# P-MT3620RDB-1-0_FTDI.net
KiCad netlist of a schematic drawn in Altium Designer
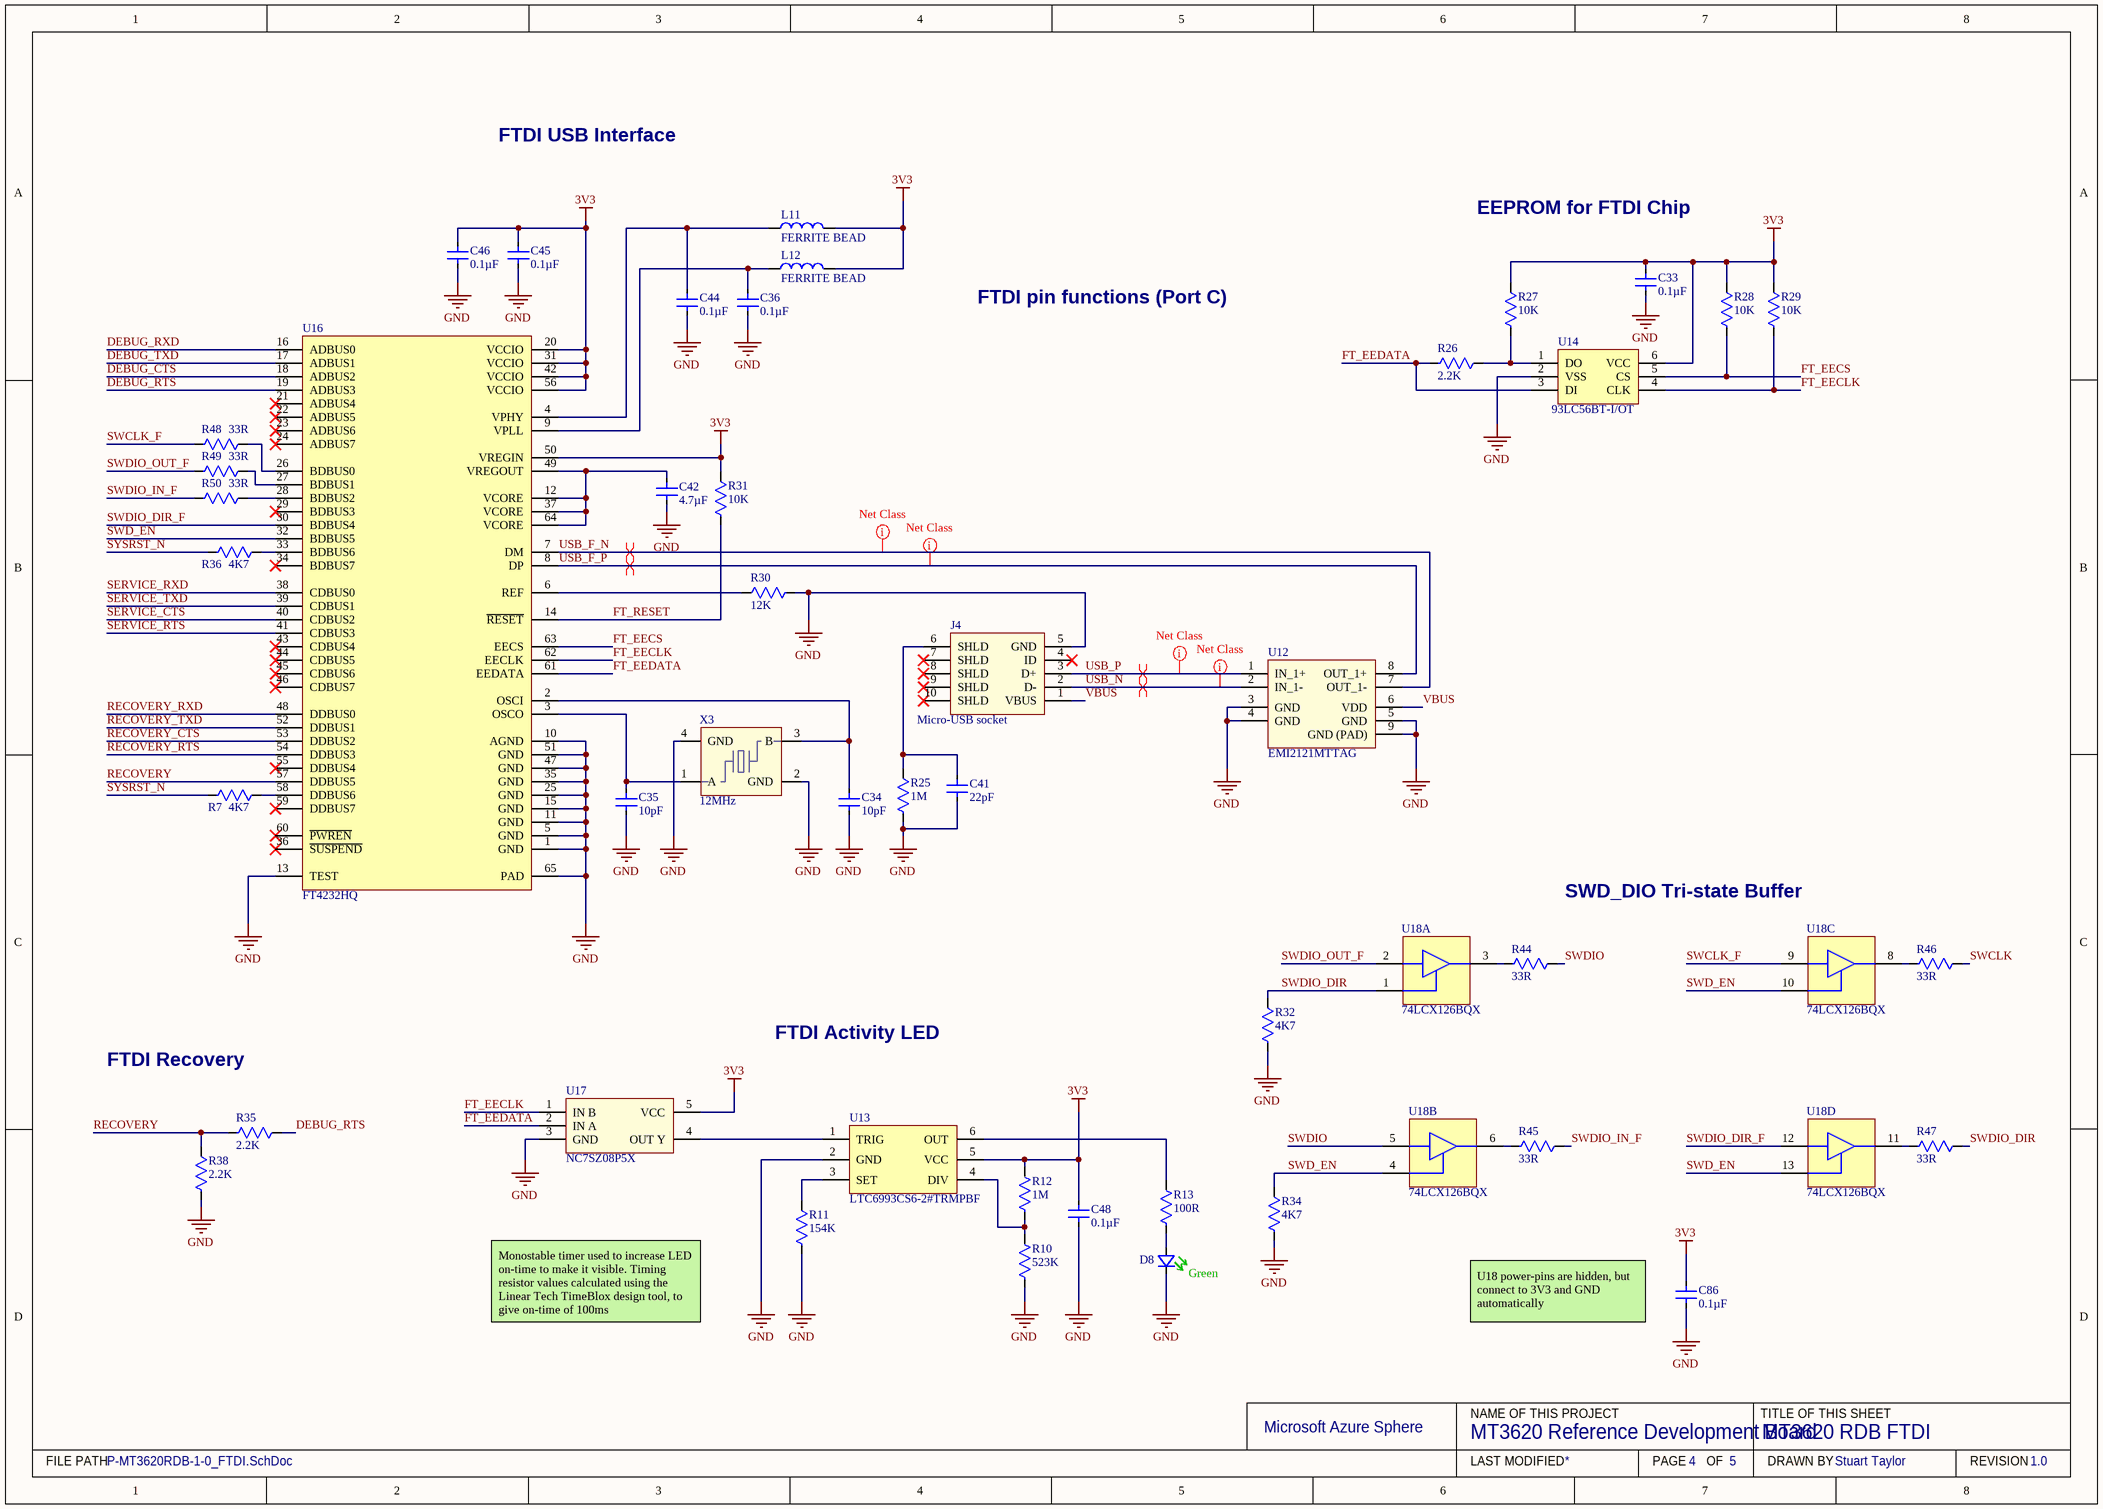
[diagram p0: P-MT3620RDB-1-0_FTDI.SchDoc]

(export (version "E")
  (design (tool "Eeschema 10.0.6"))
  (components
    (comp (ref "C33")
      (value "0.1µF")
      (footprint "CAPC1005-EIA0402 0.55MM MED")
      (description "CAP CER 0.1UF 50V 10% X7R 0402")
      (fields
        (field (name "MANUFACTURER") "TDK Corporation")
        (field (name "MANUFACTURER PART NUMBER") "C1005X7R1H104K050BB")
        (field (name "CAPACITANCE") "0.1µF")
      )
      (libsource (lib "TDK_Capacitor_C_0402") (part "0.1µF 0402 X7R 50V"))
    )
    (comp (ref "C34")
      (value "10pF")
      (footprint "CAPC1005-EIA0402 0.55MM MED")
      (description "CAP CER 10PF 50V NP0 0402")
      (fields
        (field (name "MANUFACTURER") "TDK Corporation")
        (field (name "MANUFACTURER PART NUMBER") "C1005C0G1H100D050BA")
        (field (name "CAPACITANCE") "10pF")
      )
      (libsource (lib "TDK_Capacitor_C_0402") (part "10pF 0402 C0G, NP0 50V"))
    )
    (comp (ref "C35")
      (value "10pF")
      (footprint "CAPC1005-EIA0402 0.55MM MED")
      (description "CAP CER 10PF 50V NP0 0402")
      (fields
        (field (name "MANUFACTURER") "TDK Corporation")
        (field (name "MANUFACTURER PART NUMBER") "C1005C0G1H100D050BA")
        (field (name "CAPACITANCE") "10pF")
      )
      (libsource (lib "TDK_Capacitor_C_0402") (part "10pF 0402 C0G, NP0 50V"))
    )
    (comp (ref "C36")
      (value "0.1µF")
      (footprint "CAPC1005-EIA0402 0.55MM MED")
      (description "CAP CER 0.1UF 50V 10% X7R 0402")
      (fields
        (field (name "MANUFACTURER") "TDK Corporation")
        (field (name "MANUFACTURER PART NUMBER") "C1005X7R1H104K050BB")
        (field (name "CAPACITANCE") "0.1µF")
      )
      (libsource (lib "TDK_Capacitor_C_0402") (part "0.1µF 0402 X7R 50V"))
    )
    (comp (ref "C41")
      (value "22pF")
      (footprint "CAPC1005-EIA0402 0.55MM MED")
      (description "CAP CER 22PF 50V 5% NP0 0402")
      (fields
        (field (name "MANUFACTURER") "TDK Corporation")
        (field (name "MANUFACTURER PART NUMBER") "C1005C0G1H220J050BA")
        (field (name "CAPACITANCE") "22pF")
      )
      (libsource (lib "TDK_Capacitor_C_0402") (part "22pF 0402 C0G, NP0 50V"))
    )
    (comp (ref "C42")
      (value "4.7µF")
      (footprint "CAPC1005-EIA0402 0.55MM MED")
      (description "CAP CER 4.7UF 10V 10% X5R 0402")
      (fields
        (field (name "MANUFACTURER") "TDK Corporation")
        (field (name "MANUFACTURER PART NUMBER") "C1005X5R1A475K050BC")
        (field (name "CAPACITANCE") "4.7µF")
      )
      (libsource (lib "TDK_Capacitor_C_0402") (part "4.7µF 0402 X5R 10V"))
    )
    (comp (ref "C44")
      (value "0.1µF")
      (footprint "CAPC1005-EIA0402 0.55MM MED")
      (description "CAP CER 0.1UF 50V 10% X7R 0402")
      (fields
        (field (name "MANUFACTURER") "TDK Corporation")
        (field (name "MANUFACTURER PART NUMBER") "C1005X7R1H104K050BB")
        (field (name "CAPACITANCE") "0.1µF")
      )
      (libsource (lib "TDK_Capacitor_C_0402") (part "0.1µF 0402 X7R 50V"))
    )
    (comp (ref "C45")
      (value "0.1µF")
      (footprint "CAPC1005-EIA0402 0.55MM MED")
      (description "CAP CER 0.1UF 50V 10% X7R 0402")
      (fields
        (field (name "MANUFACTURER") "TDK Corporation")
        (field (name "MANUFACTURER PART NUMBER") "C1005X7R1H104K050BB")
        (field (name "CAPACITANCE") "0.1µF")
      )
      (libsource (lib "TDK_Capacitor_C_0402") (part "0.1µF 0402 X7R 50V"))
    )
    (comp (ref "C46")
      (value "0.1µF")
      (footprint "CAPC1005-EIA0402 0.55MM MED")
      (description "CAP CER 0.1UF 50V 10% X7R 0402")
      (fields
        (field (name "MANUFACTURER") "TDK Corporation")
        (field (name "MANUFACTURER PART NUMBER") "C1005X7R1H104K050BB")
        (field (name "CAPACITANCE") "0.1µF")
      )
      (libsource (lib "TDK_Capacitor_C_0402") (part "0.1µF 0402 X7R 50V"))
    )
    (comp (ref "C48")
      (value "0.1µF")
      (footprint "CAPC1005-EIA0402 0.55MM MED")
      (description "CAP CER 0.1UF 50V 10% X7R 0402")
      (fields
        (field (name "MANUFACTURER") "TDK Corporation")
        (field (name "MANUFACTURER PART NUMBER") "C1005X7R1H104K050BB")
        (field (name "CAPACITANCE") "0.1µF")
      )
      (libsource (lib "TDK_Capacitor_C_0402") (part "0.1µF 0402 X7R 50V"))
    )
    (comp (ref "C86")
      (value "0.1µF")
      (footprint "CAPC1005-EIA0402 0.55MM MED")
      (description "CAP CER 0.1UF 50V 10% X7R 0402")
      (fields
        (field (name "MANUFACTURER") "TDK Corporation")
        (field (name "MANUFACTURER PART NUMBER") "C1005X7R1H104K050BB")
        (field (name "CAPACITANCE") "0.1µF")
      )
      (libsource (lib "TDK_Capacitor_C_0402") (part "0.1µF 0402 X7R 50V"))
    )
    (comp (ref "D8")
      (value "Green LED")
      (footprint "Rohm SML-D12 Green")
      (description "1.6 x 0.8 x 0.55mm (0603) LED 560nm Green")
      (fields
        (field (name "MANUFACTURER") "Rohm Semiconductor")
        (field (name "MANUFACTURER PART NUMBER") "SML-D12P8WT86")
        (field (name "COLOUR") "Green")
      )
      (libsource (lib "Rohm") (part "SML-D12P"))
    )
    (comp (ref "J4")
      (value "Micro-USB socket")
      (footprint "MCR-B-S-RA-SMT-CS5-T/R")
      (fields
        (field (name "MANUFACTURER") "Adam Tech")
        (field (name "MANUFACTURERS PART NUMBER") "MCR-B-S-RA-SMT-CS5-T/R")
      )
      (libsource (lib "AdamTech") (part "MCR-B-S-RA-SMT-CS5-T/R"))
    )
    (comp (ref "L11")
      (value "FERRITE BEAD")
      (footprint "CAPC1005-EIA0402 0.55MM MED")
      (description "FERRITE BEAD 120 OHM 0402 1LN")
      (fields
        (field (name "MANUFACTURER") "Murata Electronics North America")
        (field (name "MANUFACTURER PART NUMBER") "BLM15PD121SN1D")
      )
      (libsource (lib "Murata") (part "BLM15PD121SN1D"))
    )
    (comp (ref "L12")
      (value "FERRITE BEAD")
      (footprint "CAPC1005-EIA0402 0.55MM MED")
      (description "FERRITE BEAD 120 OHM 0402 1LN")
      (fields
        (field (name "MANUFACTURER") "Murata Electronics North America")
        (field (name "MANUFACTURER PART NUMBER") "BLM15PD121SN1D")
      )
      (libsource (lib "Murata") (part "BLM15PD121SN1D"))
    )
    (comp (ref "R7")
      (value "4K7")
      (footprint "RES 0402 MEDIUM DENSITY")
      (description "RES 4.7K OHM 1/10W 1% 0402 SMD")
      (fields
        (field (name "MANUFACTURER") "Panasonic Electronic Components")
        (field (name "MANUFACTURER PART NUMBER") "ERJ-2RKF4701X")
        (field (name "RESISTANCE (OHMS)") "4K7")
      )
      (libsource (lib "Panasonic_Resistor_ERJ2R") (part "4.7K"))
    )
    (comp (ref "R10")
      (value "523K")
      (footprint "RES 0402 MEDIUM DENSITY")
      (description "RES 523K OHM 1/10W 1% 0402 SMD")
      (fields
        (field (name "MANUFACTURER") "Panasonic Electronic Components")
        (field (name "MANUFACTURER PART NUMBER") "ERJ-2RKF5233X")
        (field (name "RESISTANCE (OHMS)") "523K")
      )
      (libsource (lib "Panasonic_Resistor_ERJ2R") (part "523K"))
    )
    (comp (ref "R11")
      (value "154K")
      (footprint "RES 0402 MEDIUM DENSITY")
      (description "RES 154K OHM 1/10W 1% 0402 SMD")
      (fields
        (field (name "MANUFACTURER") "Panasonic Electronic Components")
        (field (name "MANUFACTURER PART NUMBER") "ERJ-2RKF1543X")
        (field (name "RESISTANCE (OHMS)") "154K")
      )
      (libsource (lib "Panasonic_Resistor_ERJ2R") (part "154K"))
    )
    (comp (ref "R12")
      (value "1M")
      (footprint "RES 0402 MEDIUM DENSITY")
      (description "RES 1M OHM 1/10W 1% 0402 SMD")
      (fields
        (field (name "MANUFACTURER") "Panasonic Electronic Components")
        (field (name "MANUFACTURER PART NUMBER") "ERJ-2RKF1004X")
        (field (name "RESISTANCE (OHMS)") "1M")
      )
      (libsource (lib "Panasonic_Resistor_ERJ2R") (part "1M"))
    )
    (comp (ref "R13")
      (value "100R")
      (footprint "RES 0402 MEDIUM DENSITY")
      (description "RES 100 OHM 1/10W 1% 0402 SMD")
      (fields
        (field (name "MANUFACTURER") "Panasonic Electronic Components")
        (field (name "MANUFACTURER PART NUMBER") "ERJ-2RKF1000X")
        (field (name "RESISTANCE (OHMS)") "100R")
      )
      (libsource (lib "Panasonic_Resistor_ERJ2R") (part "100R"))
    )
    (comp (ref "R25")
      (value "1M")
      (footprint "RES 0402 MEDIUM DENSITY")
      (description "RES 1M OHM 1/10W 1% 0402 SMD")
      (fields
        (field (name "MANUFACTURER") "Panasonic Electronic Components")
        (field (name "MANUFACTURER PART NUMBER") "ERJ-2RKF1004X")
        (field (name "RESISTANCE (OHMS)") "1M")
      )
      (libsource (lib "Panasonic_Resistor_ERJ2R") (part "1M"))
    )
    (comp (ref "R26")
      (value "2.2K")
      (footprint "RES 0402 MEDIUM DENSITY")
      (description "RES 2.2K OHM 1/10W 1% 0402 SMD")
      (fields
        (field (name "MANUFACTURER") "Panasonic Electronic Components")
        (field (name "MANUFACTURER PART NUMBER") "ERJ-2RKF2201X")
        (field (name "RESISTANCE (OHMS)") "2.2K")
      )
      (libsource (lib "Panasonic_Resistor_ERJ2R") (part "2.2K"))
    )
    (comp (ref "R27")
      (value "10K")
      (footprint "RES 0402 MEDIUM DENSITY")
      (description "RES 10K OHM 1/10W 1% 0402 SMD")
      (fields
        (field (name "MANUFACTURER") "Panasonic Electronic Components")
        (field (name "MANUFACTURER PART NUMBER") "ERJ-2RKF1002X")
        (field (name "RESISTANCE (OHMS)") "10K")
      )
      (libsource (lib "Panasonic_Resistor_ERJ2R") (part "10K"))
    )
    (comp (ref "R28")
      (value "10K")
      (footprint "RES 0402 MEDIUM DENSITY")
      (description "RES 10K OHM 1/10W 1% 0402 SMD")
      (fields
        (field (name "MANUFACTURER") "Panasonic Electronic Components")
        (field (name "MANUFACTURER PART NUMBER") "ERJ-2RKF1002X")
        (field (name "RESISTANCE (OHMS)") "10K")
      )
      (libsource (lib "Panasonic_Resistor_ERJ2R") (part "10K"))
    )
    (comp (ref "R29")
      (value "10K")
      (footprint "RES 0402 MEDIUM DENSITY")
      (description "RES 10K OHM 1/10W 1% 0402 SMD")
      (fields
        (field (name "MANUFACTURER") "Panasonic Electronic Components")
        (field (name "MANUFACTURER PART NUMBER") "ERJ-2RKF1002X")
        (field (name "RESISTANCE (OHMS)") "10K")
      )
      (libsource (lib "Panasonic_Resistor_ERJ2R") (part "10K"))
    )
    (comp (ref "R30")
      (value "12K")
      (footprint "RES 0402 MEDIUM DENSITY")
      (description "RES 12K OHM 1/10W 1% 0402 SMD")
      (fields
        (field (name "MANUFACTURER") "Panasonic Electronic Components")
        (field (name "MANUFACTURER PART NUMBER") "ERJ-2RKF1202X")
        (field (name "RESISTANCE (OHMS)") "12K")
      )
      (libsource (lib "Panasonic_Resistor_ERJ2R") (part "12K"))
    )
    (comp (ref "R31")
      (value "10K")
      (footprint "RES 0402 MEDIUM DENSITY")
      (description "RES 10K OHM 1/10W 1% 0402 SMD")
      (fields
        (field (name "MANUFACTURER") "Panasonic Electronic Components")
        (field (name "MANUFACTURER PART NUMBER") "ERJ-2RKF1002X")
        (field (name "RESISTANCE (OHMS)") "10K")
      )
      (libsource (lib "Panasonic_Resistor_ERJ2R") (part "10K"))
    )
    (comp (ref "R32")
      (value "4K7")
      (footprint "RES 0402 MEDIUM DENSITY")
      (description "RES 4.7K OHM 1/10W 1% 0402 SMD")
      (fields
        (field (name "MANUFACTURER") "Panasonic Electronic Components")
        (field (name "MANUFACTURER PART NUMBER") "ERJ-2RKF4701X")
        (field (name "RESISTANCE (OHMS)") "4K7")
      )
      (libsource (lib "Panasonic_Resistor_ERJ2R") (part "4.7K"))
    )
    (comp (ref "R34")
      (value "4K7")
      (footprint "RES 0402 MEDIUM DENSITY")
      (description "RES 4.7K OHM 1/10W 1% 0402 SMD")
      (fields
        (field (name "MANUFACTURER") "Panasonic Electronic Components")
        (field (name "MANUFACTURER PART NUMBER") "ERJ-2RKF4701X")
        (field (name "RESISTANCE (OHMS)") "4K7")
      )
      (libsource (lib "Panasonic_Resistor_ERJ2R") (part "4.7K"))
    )
    (comp (ref "R35")
      (value "2.2K")
      (footprint "RES 0402 MEDIUM DENSITY")
      (description "RES 2.2K OHM 1/10W 1% 0402 SMD")
      (fields
        (field (name "MANUFACTURER") "Panasonic Electronic Components")
        (field (name "MANUFACTURER PART NUMBER") "ERJ-2RKF2201X")
        (field (name "RESISTANCE (OHMS)") "2.2K")
      )
      (libsource (lib "Panasonic_Resistor_ERJ2R") (part "2.2K"))
    )
    (comp (ref "R36")
      (value "4K7")
      (footprint "RES 0402 MEDIUM DENSITY")
      (description "RES 4.7K OHM 1/10W 1% 0402 SMD")
      (fields
        (field (name "MANUFACTURER") "Panasonic Electronic Components")
        (field (name "MANUFACTURER PART NUMBER") "ERJ-2RKF4701X")
        (field (name "RESISTANCE (OHMS)") "4K7")
      )
      (libsource (lib "Panasonic_Resistor_ERJ2R") (part "4.7K"))
    )
    (comp (ref "R38")
      (value "2.2K")
      (footprint "RES 0402 MEDIUM DENSITY")
      (description "RES 2.2K OHM 1/10W 1% 0402 SMD")
      (fields
        (field (name "MANUFACTURER") "Panasonic Electronic Components")
        (field (name "MANUFACTURER PART NUMBER") "ERJ-2RKF2201X")
        (field (name "RESISTANCE (OHMS)") "2.2K")
      )
      (libsource (lib "Panasonic_Resistor_ERJ2R") (part "2.2K"))
    )
    (comp (ref "R44")
      (value "33R")
      (footprint "RES 0402 MEDIUM DENSITY")
      (description "RES 33 OHM 1/10W 1% 0402 SMD")
      (fields
        (field (name "MANUFACTURER") "Panasonic Electronic Components")
        (field (name "MANUFACTURER PART NUMBER") "ERJ-2RKF33R0X")
        (field (name "RESISTANCE (OHMS)") "33R")
      )
      (libsource (lib "Panasonic_Resistor_ERJ2R") (part "33R"))
    )
    (comp (ref "R45")
      (value "33R")
      (footprint "RES 0402 MEDIUM DENSITY")
      (description "RES 33 OHM 1/10W 1% 0402 SMD")
      (fields
        (field (name "MANUFACTURER") "Panasonic Electronic Components")
        (field (name "MANUFACTURER PART NUMBER") "ERJ-2RKF33R0X")
        (field (name "RESISTANCE (OHMS)") "33R")
      )
      (libsource (lib "Panasonic_Resistor_ERJ2R") (part "33R"))
    )
    (comp (ref "R46")
      (value "33R")
      (footprint "RES 0402 MEDIUM DENSITY")
      (description "RES 33 OHM 1/10W 1% 0402 SMD")
      (fields
        (field (name "MANUFACTURER") "Panasonic Electronic Components")
        (field (name "MANUFACTURER PART NUMBER") "ERJ-2RKF33R0X")
        (field (name "RESISTANCE (OHMS)") "33R")
      )
      (libsource (lib "Panasonic_Resistor_ERJ2R") (part "33R"))
    )
    (comp (ref "R47")
      (value "33R")
      (footprint "RES 0402 MEDIUM DENSITY")
      (description "RES 33 OHM 1/10W 1% 0402 SMD")
      (fields
        (field (name "MANUFACTURER") "Panasonic Electronic Components")
        (field (name "MANUFACTURER PART NUMBER") "ERJ-2RKF33R0X")
        (field (name "RESISTANCE (OHMS)") "33R")
      )
      (libsource (lib "Panasonic_Resistor_ERJ2R") (part "33R"))
    )
    (comp (ref "R48")
      (value "33R")
      (footprint "RES 0402 MEDIUM DENSITY")
      (description "RES 33 OHM 1/10W 1% 0402 SMD")
      (fields
        (field (name "MANUFACTURER") "Panasonic Electronic Components")
        (field (name "MANUFACTURER PART NUMBER") "ERJ-2RKF33R0X")
        (field (name "RESISTANCE (OHMS)") "33R")
      )
      (libsource (lib "Panasonic_Resistor_ERJ2R") (part "33R"))
    )
    (comp (ref "R49")
      (value "33R")
      (footprint "RES 0402 MEDIUM DENSITY")
      (description "RES 33 OHM 1/10W 1% 0402 SMD")
      (fields
        (field (name "MANUFACTURER") "Panasonic Electronic Components")
        (field (name "MANUFACTURER PART NUMBER") "ERJ-2RKF33R0X")
        (field (name "RESISTANCE (OHMS)") "33R")
      )
      (libsource (lib "Panasonic_Resistor_ERJ2R") (part "33R"))
    )
    (comp (ref "R50")
      (value "33R")
      (footprint "RES 0402 MEDIUM DENSITY")
      (description "RES 33 OHM 1/10W 1% 0402 SMD")
      (fields
        (field (name "MANUFACTURER") "Panasonic Electronic Components")
        (field (name "MANUFACTURER PART NUMBER") "ERJ-2RKF33R0X")
        (field (name "RESISTANCE (OHMS)") "33R")
      )
      (libsource (lib "Panasonic_Resistor_ERJ2R") (part "33R"))
    )
    (comp (ref "U12")
      (value "EMI2121MTTAG")
      (footprint "EMI2121MTTAG")
      (description "IC FILTER COMMON MODE ESD 8WDFN")
      (fields (field (name "MANUFACTURER") "ON Semiconductor"))
      (libsource (lib "OnSemiconductor") (part "EMI2121MTTAG"))
    )
    (comp (ref "U13")
      (value "LTC6993CS6-2#TRMPBF")
      (footprint "LTC6993CS6-2#TRMPBF")
      (description "LINEAR TECHNOLOGY - LTC6993CS6-2#TRMPBF - GENERATOR, PULSE, TIMERBLOX, 6SOT-23")
      (fields (field (name "MANUFACTURER") "LINEAR TECHNOLOGY"))
      (libsource (lib "LinearTech") (part "LTC6993CS6-2#TRMPBF"))
    )
    (comp (ref "U14")
      (value "93LC56BT-I/OT")
      (footprint "SOT23-93C56B")
      (description "IC EEPROM 2KBIT 2MHZ SOT23-6")
      (fields (field (name "MANUFACTURER") "Microchip Technology"))
      (libsource (lib "Microchip") (part "93LC56BT-I/OT"))
    )
    (comp (ref "U16")
      (value "FT4232HQ")
      (footprint "FTDI_TF4232HQ_64QFN")
      (description "IC USB HS QUAD UART/SYNC 64-QFN")
      (fields
        (field (name "MANUFACTURER") "FTDI, Future Technology Devices International Ltd")
        (field (name "MANUFACTURER PART NUMBER") "FT4232HQ-REEL")
      )
      (libsource (lib "FTDI") (part "FT4232HQ"))
    )
    (comp (ref "U17")
      (value "NC7SZ08P5X")
      (footprint "SC-70-5")
      (description "IC GATE AND 1CH 2-INP SC-70-5")
      (fields (field (name "MANUFACTURER") "Fairchild Semiconductor"))
      (libsource (lib "OnSemiconductor") (part "NC7SZ08P5X"))
    )
    (comp (ref "U18")
      (value "74LCX126BQX")
      (footprint "74LCX126BQX")
      (description "IC BUFFER QUAD LV N-INV 14DQFN")
      (fields (field (name "MANUFACTURER") "Fairchild Semiconductor"))
      (libsource (lib "OnSemiconductor") (part "74LCX126BQX"))
    )
    (comp (ref "X3")
      (value "12MHz")
      (footprint "TXC 8Z")
      (description "CRYSTAL 12.000 MHZ 18PF SMD")
      (fields
        (field (name "MANUFACTURER") "TXC CORPORATION")
        (field (name "MANUFACTURER PART NUMBER") "8Z-12.000MAAJ-T")
        (field (name "FREQUENCY") "12MHz")
      )
      (libsource (lib "crystal") (part "CRYSTAL 12MHz 18pF SMD"))
    )
  )
  (nets
    (net (code "1") (name "/DEBUG_CTS") (class "Default")
      (node (ref "U16") (pin "18") (pinfunction "ADBUS2_18") (pintype "passive"))
    )
    (net (code "2") (name "/DEBUG_RTS") (class "Default")
      (node (ref "R35") (pin "1") (pinfunction "1_1") (pintype "passive"))
      (node (ref "U16") (pin "19") (pinfunction "ADBUS3_19") (pintype "passive"))
    )
    (net (code "3") (name "/DEBUG_RXD") (class "Default")
      (node (ref "U16") (pin "16") (pinfunction "ADBUS0_16") (pintype "passive"))
    )
    (net (code "4") (name "/DEBUG_TXD") (class "Default")
      (node (ref "U16") (pin "17") (pinfunction "ADBUS1_17") (pintype "passive"))
    )
    (net (code "5") (name "/FT_EECLK") (class "Default")
      (node (ref "R29") (pin "2") (pinfunction "2_2") (pintype "passive"))
      (node (ref "U14") (pin "4") (pinfunction "CLK_4") (pintype "passive"))
      (node (ref "U16") (pin "62") (pinfunction "EECLK_62") (pintype "passive"))
      (node (ref "U17") (pin "1") (pinfunction "IN_B_1") (pintype "passive"))
    )
    (net (code "6") (name "/FT_EECS") (class "Default")
      (node (ref "R28") (pin "2") (pinfunction "2_2") (pintype "passive"))
      (node (ref "U14") (pin "5") (pinfunction "CS_5") (pintype "passive"))
      (node (ref "U16") (pin "63") (pinfunction "EECS_63") (pintype "passive"))
    )
    (net (code "7") (name "/FT_EEDATA") (class "Default")
      (node (ref "R26") (pin "2") (pinfunction "2_2") (pintype "passive"))
      (node (ref "U14") (pin "3") (pinfunction "DI_3") (pintype "passive"))
      (node (ref "U16") (pin "61") (pinfunction "EEDATA_61") (pintype "passive"))
      (node (ref "U17") (pin "2") (pinfunction "IN_A_2") (pintype "passive"))
    )
    (net (code "8") (name "/FT_RESET") (class "Default")
      (node (ref "R31") (pin "2") (pinfunction "2_2") (pintype "passive"))
      (node (ref "U16") (pin "14") (pinfunction "~{RESET}_14") (pintype "passive"))
    )
    (net (code "9") (name "/RECOVERY") (class "Default")
      (node (ref "R35") (pin "2") (pinfunction "2_2") (pintype "passive"))
      (node (ref "R38") (pin "1") (pinfunction "1_1") (pintype "passive"))
      (node (ref "U16") (pin "57") (pinfunction "DDBUS5_57") (pintype "passive"))
    )
    (net (code "10") (name "/RECOVERY_CTS") (class "Default")
      (node (ref "U16") (pin "53") (pinfunction "DDBUS2_53") (pintype "passive"))
    )
    (net (code "11") (name "/RECOVERY_RTS") (class "Default")
      (node (ref "U16") (pin "54") (pinfunction "DDBUS3_54") (pintype "passive"))
    )
    (net (code "12") (name "/RECOVERY_RXD") (class "Default")
      (node (ref "U16") (pin "48") (pinfunction "DDBUS0_48") (pintype "passive"))
    )
    (net (code "13") (name "/RECOVERY_TXD") (class "Default")
      (node (ref "U16") (pin "52") (pinfunction "DDBUS1_52") (pintype "passive"))
    )
    (net (code "14") (name "/SERVICE_CTS") (class "Default")
      (node (ref "U16") (pin "40") (pinfunction "CDBUS2_40") (pintype "passive"))
    )
    (net (code "15") (name "/SERVICE_RTS") (class "Default")
      (node (ref "U16") (pin "41") (pinfunction "CDBUS3_41") (pintype "passive"))
    )
    (net (code "16") (name "/SERVICE_RXD") (class "Default")
      (node (ref "U16") (pin "38") (pinfunction "CDBUS0_38") (pintype "passive"))
    )
    (net (code "17") (name "/SERVICE_TXD") (class "Default")
      (node (ref "U16") (pin "39") (pinfunction "CDBUS1_39") (pintype "passive"))
    )
    (net (code "18") (name "/SWCLK") (class "Default")
      (node (ref "R46") (pin "1") (pinfunction "1_1") (pintype "passive"))
    )
    (net (code "19") (name "/SWCLK_F") (class "Default")
      (node (ref "R48") (pin "2") (pinfunction "2_2") (pintype "passive"))
      (node (ref "U18") (pin "9") (pinfunction "3A_9") (pintype "passive"))
    )
    (net (code "20") (name "/SWDIO") (class "Default")
      (node (ref "R44") (pin "1") (pinfunction "1_1") (pintype "passive"))
      (node (ref "U18") (pin "5") (pinfunction "2A_5") (pintype "passive"))
    )
    (net (code "21") (name "/SWDIO_DIR") (class "Default")
      (node (ref "R32") (pin "1") (pinfunction "1_1") (pintype "passive"))
      (node (ref "R47") (pin "1") (pinfunction "1_1") (pintype "passive"))
      (node (ref "U18") (pin "1") (pinfunction "1OE_1") (pintype "passive"))
    )
    (net (code "22") (name "/SWDIO_DIR_F") (class "Default")
      (node (ref "U16") (pin "30") (pinfunction "BDBUS4_30") (pintype "passive"))
      (node (ref "U18") (pin "12") (pinfunction "4A_12") (pintype "passive"))
    )
    (net (code "23") (name "/SWDIO_IN_F") (class "Default")
      (node (ref "R45") (pin "1") (pinfunction "1_1") (pintype "passive"))
      (node (ref "R50") (pin "2") (pinfunction "2_2") (pintype "passive"))
    )
    (net (code "24") (name "/SWDIO_OUT_F") (class "Default")
      (node (ref "R49") (pin "2") (pinfunction "2_2") (pintype "passive"))
      (node (ref "U18") (pin "2") (pinfunction "1A_2") (pintype "passive"))
    )
    (net (code "25") (name "/SWD_EN") (class "Default")
      (node (ref "R34") (pin "1") (pinfunction "1_1") (pintype "passive"))
      (node (ref "U16") (pin "32") (pinfunction "BDBUS5_32") (pintype "passive"))
      (node (ref "U18") (pin "10") (pinfunction "3OE_10") (pintype "passive"))
      (node (ref "U18") (pin "13") (pinfunction "4OE_13") (pintype "passive"))
      (node (ref "U18") (pin "4") (pinfunction "2OE_4") (pintype "passive"))
    )
    (net (code "26") (name "/SYSRST_N") (class "Default")
      (node (ref "R36") (pin "2") (pinfunction "2_2") (pintype "passive"))
      (node (ref "R7") (pin "2") (pinfunction "2_2") (pintype "passive"))
    )
    (net (code "27") (name "/USB_F_N") (class "Default")
      (node (ref "U12") (pin "7") (pinfunction "OUT_1-_7") (pintype "passive"))
      (node (ref "U16") (pin "7") (pinfunction "DM_7") (pintype "passive"))
    )
    (net (code "28") (name "/USB_F_P") (class "Default")
      (node (ref "U12") (pin "8") (pinfunction "OUT_1+_8") (pintype "passive"))
      (node (ref "U16") (pin "8") (pinfunction "DP_8") (pintype "passive"))
    )
    (net (code "29") (name "/USB_N") (class "Default")
      (node (ref "J4") (pin "2") (pinfunction "D-_2") (pintype "passive"))
      (node (ref "U12") (pin "2") (pinfunction "IN_1-_2") (pintype "passive"))
    )
    (net (code "30") (name "/USB_P") (class "Default")
      (node (ref "J4") (pin "3") (pinfunction "D+_3") (pintype "passive"))
      (node (ref "U12") (pin "1") (pinfunction "IN_1+_1") (pintype "passive"))
    )
    (net (code "31") (name "/VBUS") (class "Default")
      (node (ref "J4") (pin "1") (pinfunction "VBUS_1") (pintype "passive"))
      (node (ref "U12") (pin "6") (pinfunction "VDD_6") (pintype "passive"))
    )
    (net (code "32") (name "3V3") (class "Default")
      (node (ref "C33") (pin "2") (pinfunction "2_2") (pintype "passive"))
      (node (ref "C45") (pin "2") (pinfunction "2_2") (pintype "passive"))
      (node (ref "C46") (pin "2") (pinfunction "2_2") (pintype "passive"))
      (node (ref "C48") (pin "2") (pinfunction "2_2") (pintype "passive"))
      (node (ref "C86") (pin "2") (pinfunction "2_2") (pintype "passive"))
      (node (ref "L11") (pin "2") (pinfunction "2_2") (pintype "passive"))
      (node (ref "L12") (pin "2") (pinfunction "2_2") (pintype "passive"))
      (node (ref "R12") (pin "1") (pinfunction "1_1") (pintype "passive"))
      (node (ref "R27") (pin "1") (pinfunction "1_1") (pintype "passive"))
      (node (ref "R28") (pin "1") (pinfunction "1_1") (pintype "passive"))
      (node (ref "R29") (pin "1") (pinfunction "1_1") (pintype "passive"))
      (node (ref "R31") (pin "1") (pinfunction "1_1") (pintype "passive"))
      (node (ref "U13") (pin "5") (pinfunction "VCC_5") (pintype "passive"))
      (node (ref "U14") (pin "6") (pinfunction "VCC_6") (pintype "passive"))
      (node (ref "U16") (pin "20") (pinfunction "VCCIO_20") (pintype "passive"))
      (node (ref "U16") (pin "31") (pinfunction "VCCIO_31") (pintype "passive"))
      (node (ref "U16") (pin "42") (pinfunction "VCCIO_42") (pintype "passive"))
      (node (ref "U16") (pin "50") (pinfunction "VREGIN_50") (pintype "passive"))
      (node (ref "U16") (pin "56") (pinfunction "VCCIO_56") (pintype "passive"))
      (node (ref "U17") (pin "5") (pinfunction "VCC_5") (pintype "passive"))
      (node (ref "U18") (pin "14") (pinfunction "3V3_14") (pintype "power_in"))
    )
    (net (code "33") (name "GND") (class "Default")
      (node (ref "C33") (pin "1") (pinfunction "1_1") (pintype "passive"))
      (node (ref "C34") (pin "1") (pinfunction "1_1") (pintype "passive"))
      (node (ref "C35") (pin "1") (pinfunction "1_1") (pintype "passive"))
      (node (ref "C36") (pin "1") (pinfunction "1_1") (pintype "passive"))
      (node (ref "C41") (pin "1") (pinfunction "1_1") (pintype "passive"))
      (node (ref "C42") (pin "1") (pinfunction "1_1") (pintype "passive"))
      (node (ref "C44") (pin "1") (pinfunction "1_1") (pintype "passive"))
      (node (ref "C45") (pin "1") (pinfunction "1_1") (pintype "passive"))
      (node (ref "C46") (pin "1") (pinfunction "1_1") (pintype "passive"))
      (node (ref "C48") (pin "1") (pinfunction "1_1") (pintype "passive"))
      (node (ref "C86") (pin "1") (pinfunction "1_1") (pintype "passive"))
      (node (ref "D8") (pin "1") (pinfunction "K_1") (pintype "passive"))
      (node (ref "J4") (pin "5") (pinfunction "GND_5") (pintype "passive"))
      (node (ref "R10") (pin "2") (pinfunction "2_2") (pintype "passive"))
      (node (ref "R11") (pin "2") (pinfunction "2_2") (pintype "passive"))
      (node (ref "R25") (pin "2") (pinfunction "2_2") (pintype "passive"))
      (node (ref "R30") (pin "2") (pinfunction "2_2") (pintype "passive"))
      (node (ref "R32") (pin "2") (pinfunction "2_2") (pintype "passive"))
      (node (ref "R34") (pin "2") (pinfunction "2_2") (pintype "passive"))
      (node (ref "R38") (pin "2") (pinfunction "2_2") (pintype "passive"))
      (node (ref "U12") (pin "3") (pinfunction "GND_3") (pintype "passive"))
      (node (ref "U12") (pin "4") (pinfunction "GND_4") (pintype "passive"))
      (node (ref "U12") (pin "5") (pinfunction "GND_5") (pintype "passive"))
      (node (ref "U12") (pin "9") (pinfunction "GND_(PAD)_9") (pintype "passive"))
      (node (ref "U13") (pin "2") (pinfunction "GND_2") (pintype "passive"))
      (node (ref "U14") (pin "2") (pinfunction "VSS_2") (pintype "passive"))
      (node (ref "U16") (pin "1") (pinfunction "GND_1") (pintype "passive"))
      (node (ref "U16") (pin "10") (pinfunction "AGND_10") (pintype "passive"))
      (node (ref "U16") (pin "11") (pinfunction "GND_11") (pintype "passive"))
      (node (ref "U16") (pin "13") (pinfunction "TEST_13") (pintype "passive"))
      (node (ref "U16") (pin "15") (pinfunction "GND_15") (pintype "passive"))
      (node (ref "U16") (pin "25") (pinfunction "GND_25") (pintype "passive"))
      (node (ref "U16") (pin "35") (pinfunction "GND_35") (pintype "passive"))
      (node (ref "U16") (pin "47") (pinfunction "GND_47") (pintype "passive"))
      (node (ref "U16") (pin "5") (pinfunction "GND_5") (pintype "passive"))
      (node (ref "U16") (pin "51") (pinfunction "GND_51") (pintype "passive"))
      (node (ref "U16") (pin "65") (pinfunction "PAD_65") (pintype "passive"))
      (node (ref "U17") (pin "3") (pinfunction "GND_3") (pintype "passive"))
      (node (ref "U18") (pin "7") (pinfunction "GND_7") (pintype "power_in"))
      (node (ref "X3") (pin "2") (pinfunction "GND_2") (pintype "passive"))
      (node (ref "X3") (pin "4") (pinfunction "GND_4") (pintype "passive"))
    )
    (net (code "34") (name "Net-(C41-Pad2)") (class "Default")
      (node (ref "C41") (pin "2") (pinfunction "2_2") (pintype "passive"))
      (node (ref "J4") (pin "6") (pinfunction "SHLD_6") (pintype "passive"))
      (node (ref "R25") (pin "1") (pinfunction "1_1") (pintype "passive"))
    )
    (net (code "35") (name "Net-(D8-A)") (class "Default")
      (node (ref "D8") (pin "2") (pinfunction "A_2") (pintype "passive"))
      (node (ref "R13") (pin "2") (pinfunction "2_2") (pintype "passive"))
    )
    (net (code "36") (name "Net-(U13-DIV)") (class "Default")
      (node (ref "R10") (pin "1") (pinfunction "1_1") (pintype "passive"))
      (node (ref "R12") (pin "2") (pinfunction "2_2") (pintype "passive"))
      (node (ref "U13") (pin "4") (pinfunction "DIV_4") (pintype "passive"))
    )
    (net (code "37") (name "Net-(U13-OUT)") (class "Default")
      (node (ref "R13") (pin "1") (pinfunction "1_1") (pintype "passive"))
      (node (ref "U13") (pin "6") (pinfunction "OUT_6") (pintype "passive"))
    )
    (net (code "38") (name "Net-(U13-SET)") (class "Default")
      (node (ref "R11") (pin "1") (pinfunction "1_1") (pintype "passive"))
      (node (ref "U13") (pin "3") (pinfunction "SET_3") (pintype "passive"))
    )
    (net (code "39") (name "Net-(U13-TRIG)") (class "Default")
      (node (ref "U13") (pin "1") (pinfunction "TRIG_1") (pintype "passive"))
      (node (ref "U17") (pin "4") (pinfunction "OUT_Y_4") (pintype "passive"))
    )
    (net (code "40") (name "Net-(U14-DO)") (class "Default")
      (node (ref "R26") (pin "1") (pinfunction "1_1") (pintype "passive"))
      (node (ref "R27") (pin "2") (pinfunction "2_2") (pintype "passive"))
      (node (ref "U14") (pin "1") (pinfunction "DO_1") (pintype "passive"))
    )
    (net (code "41") (name "Net-(U16-BDBUS0)") (class "Default")
      (node (ref "R48") (pin "1") (pinfunction "1_1") (pintype "passive"))
      (node (ref "U16") (pin "26") (pinfunction "BDBUS0_26") (pintype "passive"))
    )
    (net (code "42") (name "Net-(U16-BDBUS1)") (class "Default")
      (node (ref "R49") (pin "1") (pinfunction "1_1") (pintype "passive"))
      (node (ref "U16") (pin "27") (pinfunction "BDBUS1_27") (pintype "passive"))
    )
    (net (code "43") (name "Net-(U16-BDBUS2)") (class "Default")
      (node (ref "R50") (pin "1") (pinfunction "1_1") (pintype "passive"))
      (node (ref "U16") (pin "28") (pinfunction "BDBUS2_28") (pintype "passive"))
    )
    (net (code "44") (name "Net-(U16-BDBUS6)") (class "Default")
      (node (ref "R36") (pin "1") (pinfunction "1_1") (pintype "passive"))
      (node (ref "U16") (pin "33") (pinfunction "BDBUS6_33") (pintype "passive"))
    )
    (net (code "45") (name "Net-(U16-DDBUS6)") (class "Default")
      (node (ref "R7") (pin "1") (pinfunction "1_1") (pintype "passive"))
      (node (ref "U16") (pin "58") (pinfunction "DDBUS6_58") (pintype "passive"))
    )
    (net (code "46") (name "Net-(U16-OSCI)") (class "Default")
      (node (ref "C34") (pin "2") (pinfunction "2_2") (pintype "passive"))
      (node (ref "U16") (pin "2") (pinfunction "OSCI_2") (pintype "passive"))
      (node (ref "X3") (pin "3") (pinfunction "B_3") (pintype "passive"))
    )
    (net (code "47") (name "Net-(U16-OSCO)") (class "Default")
      (node (ref "C35") (pin "2") (pinfunction "2_2") (pintype "passive"))
      (node (ref "U16") (pin "3") (pinfunction "OSCO_3") (pintype "passive"))
      (node (ref "X3") (pin "1") (pinfunction "A_1") (pintype "passive"))
    )
    (net (code "48") (name "Net-(U16-REF)") (class "Default")
      (node (ref "R30") (pin "1") (pinfunction "1_1") (pintype "passive"))
      (node (ref "U16") (pin "6") (pinfunction "REF_6") (pintype "passive"))
    )
    (net (code "49") (name "Net-(U16-VPHY)") (class "Default")
      (node (ref "C44") (pin "2") (pinfunction "2_2") (pintype "passive"))
      (node (ref "L11") (pin "1") (pinfunction "1_1") (pintype "passive"))
      (node (ref "U16") (pin "4") (pinfunction "VPHY_4") (pintype "passive"))
    )
    (net (code "50") (name "Net-(U16-VPLL)") (class "Default")
      (node (ref "C36") (pin "2") (pinfunction "2_2") (pintype "passive"))
      (node (ref "L12") (pin "1") (pinfunction "1_1") (pintype "passive"))
      (node (ref "U16") (pin "9") (pinfunction "VPLL_9") (pintype "passive"))
    )
    (net (code "51") (name "Net-(U16-VREGOUT)") (class "Default")
      (node (ref "C42") (pin "2") (pinfunction "2_2") (pintype "passive"))
      (node (ref "U16") (pin "12") (pinfunction "VCORE_12") (pintype "passive"))
      (node (ref "U16") (pin "37") (pinfunction "VCORE_37") (pintype "passive"))
      (node (ref "U16") (pin "49") (pinfunction "VREGOUT_49") (pintype "passive"))
      (node (ref "U16") (pin "64") (pinfunction "VCORE_64") (pintype "passive"))
    )
    (net (code "52") (name "Net-(U18A-1Y)") (class "Default")
      (node (ref "R44") (pin "2") (pinfunction "2_2") (pintype "passive"))
      (node (ref "U18") (pin "3") (pinfunction "1Y_3") (pintype "passive"))
    )
    (net (code "53") (name "Net-(U18B-2Y)") (class "Default")
      (node (ref "R45") (pin "2") (pinfunction "2_2") (pintype "passive"))
      (node (ref "U18") (pin "6") (pinfunction "2Y_6") (pintype "passive"))
    )
    (net (code "54") (name "Net-(U18C-3Y)") (class "Default")
      (node (ref "R46") (pin "2") (pinfunction "2_2") (pintype "passive"))
      (node (ref "U18") (pin "8") (pinfunction "3Y_8") (pintype "passive"))
    )
    (net (code "55") (name "Net-(U18D-4Y)") (class "Default")
      (node (ref "R47") (pin "2") (pinfunction "2_2") (pintype "passive"))
      (node (ref "U18") (pin "11") (pinfunction "4Y_11") (pintype "passive"))
    )
    (net (code "56") (name "unconnected-(J4-ID-Pad4)") (class "Default")
      (node (ref "J4") (pin "4") (pinfunction "ID_4") (pintype "passive+no_connect"))
    )
    (net (code "57") (name "unconnected-(J4-SHLD-Pad7)") (class "Default")
      (node (ref "J4") (pin "7") (pinfunction "SHLD_7") (pintype "passive+no_connect"))
    )
    (net (code "58") (name "unconnected-(J4-SHLD-Pad8)") (class "Default")
      (node (ref "J4") (pin "8") (pinfunction "SHLD_8") (pintype "passive+no_connect"))
    )
    (net (code "59") (name "unconnected-(J4-SHLD-Pad9)") (class "Default")
      (node (ref "J4") (pin "9") (pinfunction "SHLD_9") (pintype "passive+no_connect"))
    )
    (net (code "60") (name "unconnected-(J4-SHLD-Pad10)") (class "Default")
      (node (ref "J4") (pin "10") (pinfunction "SHLD_10") (pintype "passive+no_connect"))
    )
    (net (code "61") (name "unconnected-(U16-ADBUS4-Pad21)") (class "Default")
      (node (ref "U16") (pin "21") (pinfunction "ADBUS4_21") (pintype "passive+no_connect"))
    )
    (net (code "62") (name "unconnected-(U16-ADBUS5-Pad22)") (class "Default")
      (node (ref "U16") (pin "22") (pinfunction "ADBUS5_22") (pintype "passive+no_connect"))
    )
    (net (code "63") (name "unconnected-(U16-ADBUS6-Pad23)") (class "Default")
      (node (ref "U16") (pin "23") (pinfunction "ADBUS6_23") (pintype "passive+no_connect"))
    )
    (net (code "64") (name "unconnected-(U16-ADBUS7-Pad24)") (class "Default")
      (node (ref "U16") (pin "24") (pinfunction "ADBUS7_24") (pintype "passive+no_connect"))
    )
    (net (code "65") (name "unconnected-(U16-BDBUS3-Pad29)") (class "Default")
      (node (ref "U16") (pin "29") (pinfunction "BDBUS3_29") (pintype "passive+no_connect"))
    )
    (net (code "66") (name "unconnected-(U16-BDBUS7-Pad34)") (class "Default")
      (node (ref "U16") (pin "34") (pinfunction "BDBUS7_34") (pintype "passive+no_connect"))
    )
    (net (code "67") (name "unconnected-(U16-CDBUS4-Pad43)") (class "Default")
      (node (ref "U16") (pin "43") (pinfunction "CDBUS4_43") (pintype "passive+no_connect"))
    )
    (net (code "68") (name "unconnected-(U16-CDBUS5-Pad44)") (class "Default")
      (node (ref "U16") (pin "44") (pinfunction "CDBUS5_44") (pintype "passive+no_connect"))
    )
    (net (code "69") (name "unconnected-(U16-CDBUS6-Pad45)") (class "Default")
      (node (ref "U16") (pin "45") (pinfunction "CDBUS6_45") (pintype "passive+no_connect"))
    )
    (net (code "70") (name "unconnected-(U16-CDBUS7-Pad46)") (class "Default")
      (node (ref "U16") (pin "46") (pinfunction "CDBUS7_46") (pintype "passive+no_connect"))
    )
    (net (code "71") (name "unconnected-(U16-DDBUS4-Pad55)") (class "Default")
      (node (ref "U16") (pin "55") (pinfunction "DDBUS4_55") (pintype "passive+no_connect"))
    )
    (net (code "72") (name "unconnected-(U16-DDBUS7-Pad59)") (class "Default")
      (node (ref "U16") (pin "59") (pinfunction "DDBUS7_59") (pintype "passive+no_connect"))
    )
    (net (code "73") (name "unconnected-(U16-~{PWREN}-Pad60)") (class "Default")
      (node (ref "U16") (pin "60") (pinfunction "~{PWREN}_60") (pintype "passive+no_connect"))
    )
    (net (code "74") (name "unconnected-(U16-~{SUSPEND}-Pad36)") (class "Default")
      (node (ref "U16") (pin "36") (pinfunction "~{SUSPEND}_36") (pintype "passive+no_connect"))
    )
  )
)
